# ESP32_can.net
KiCad netlist of a schematic drawn in EasyEDA Pro
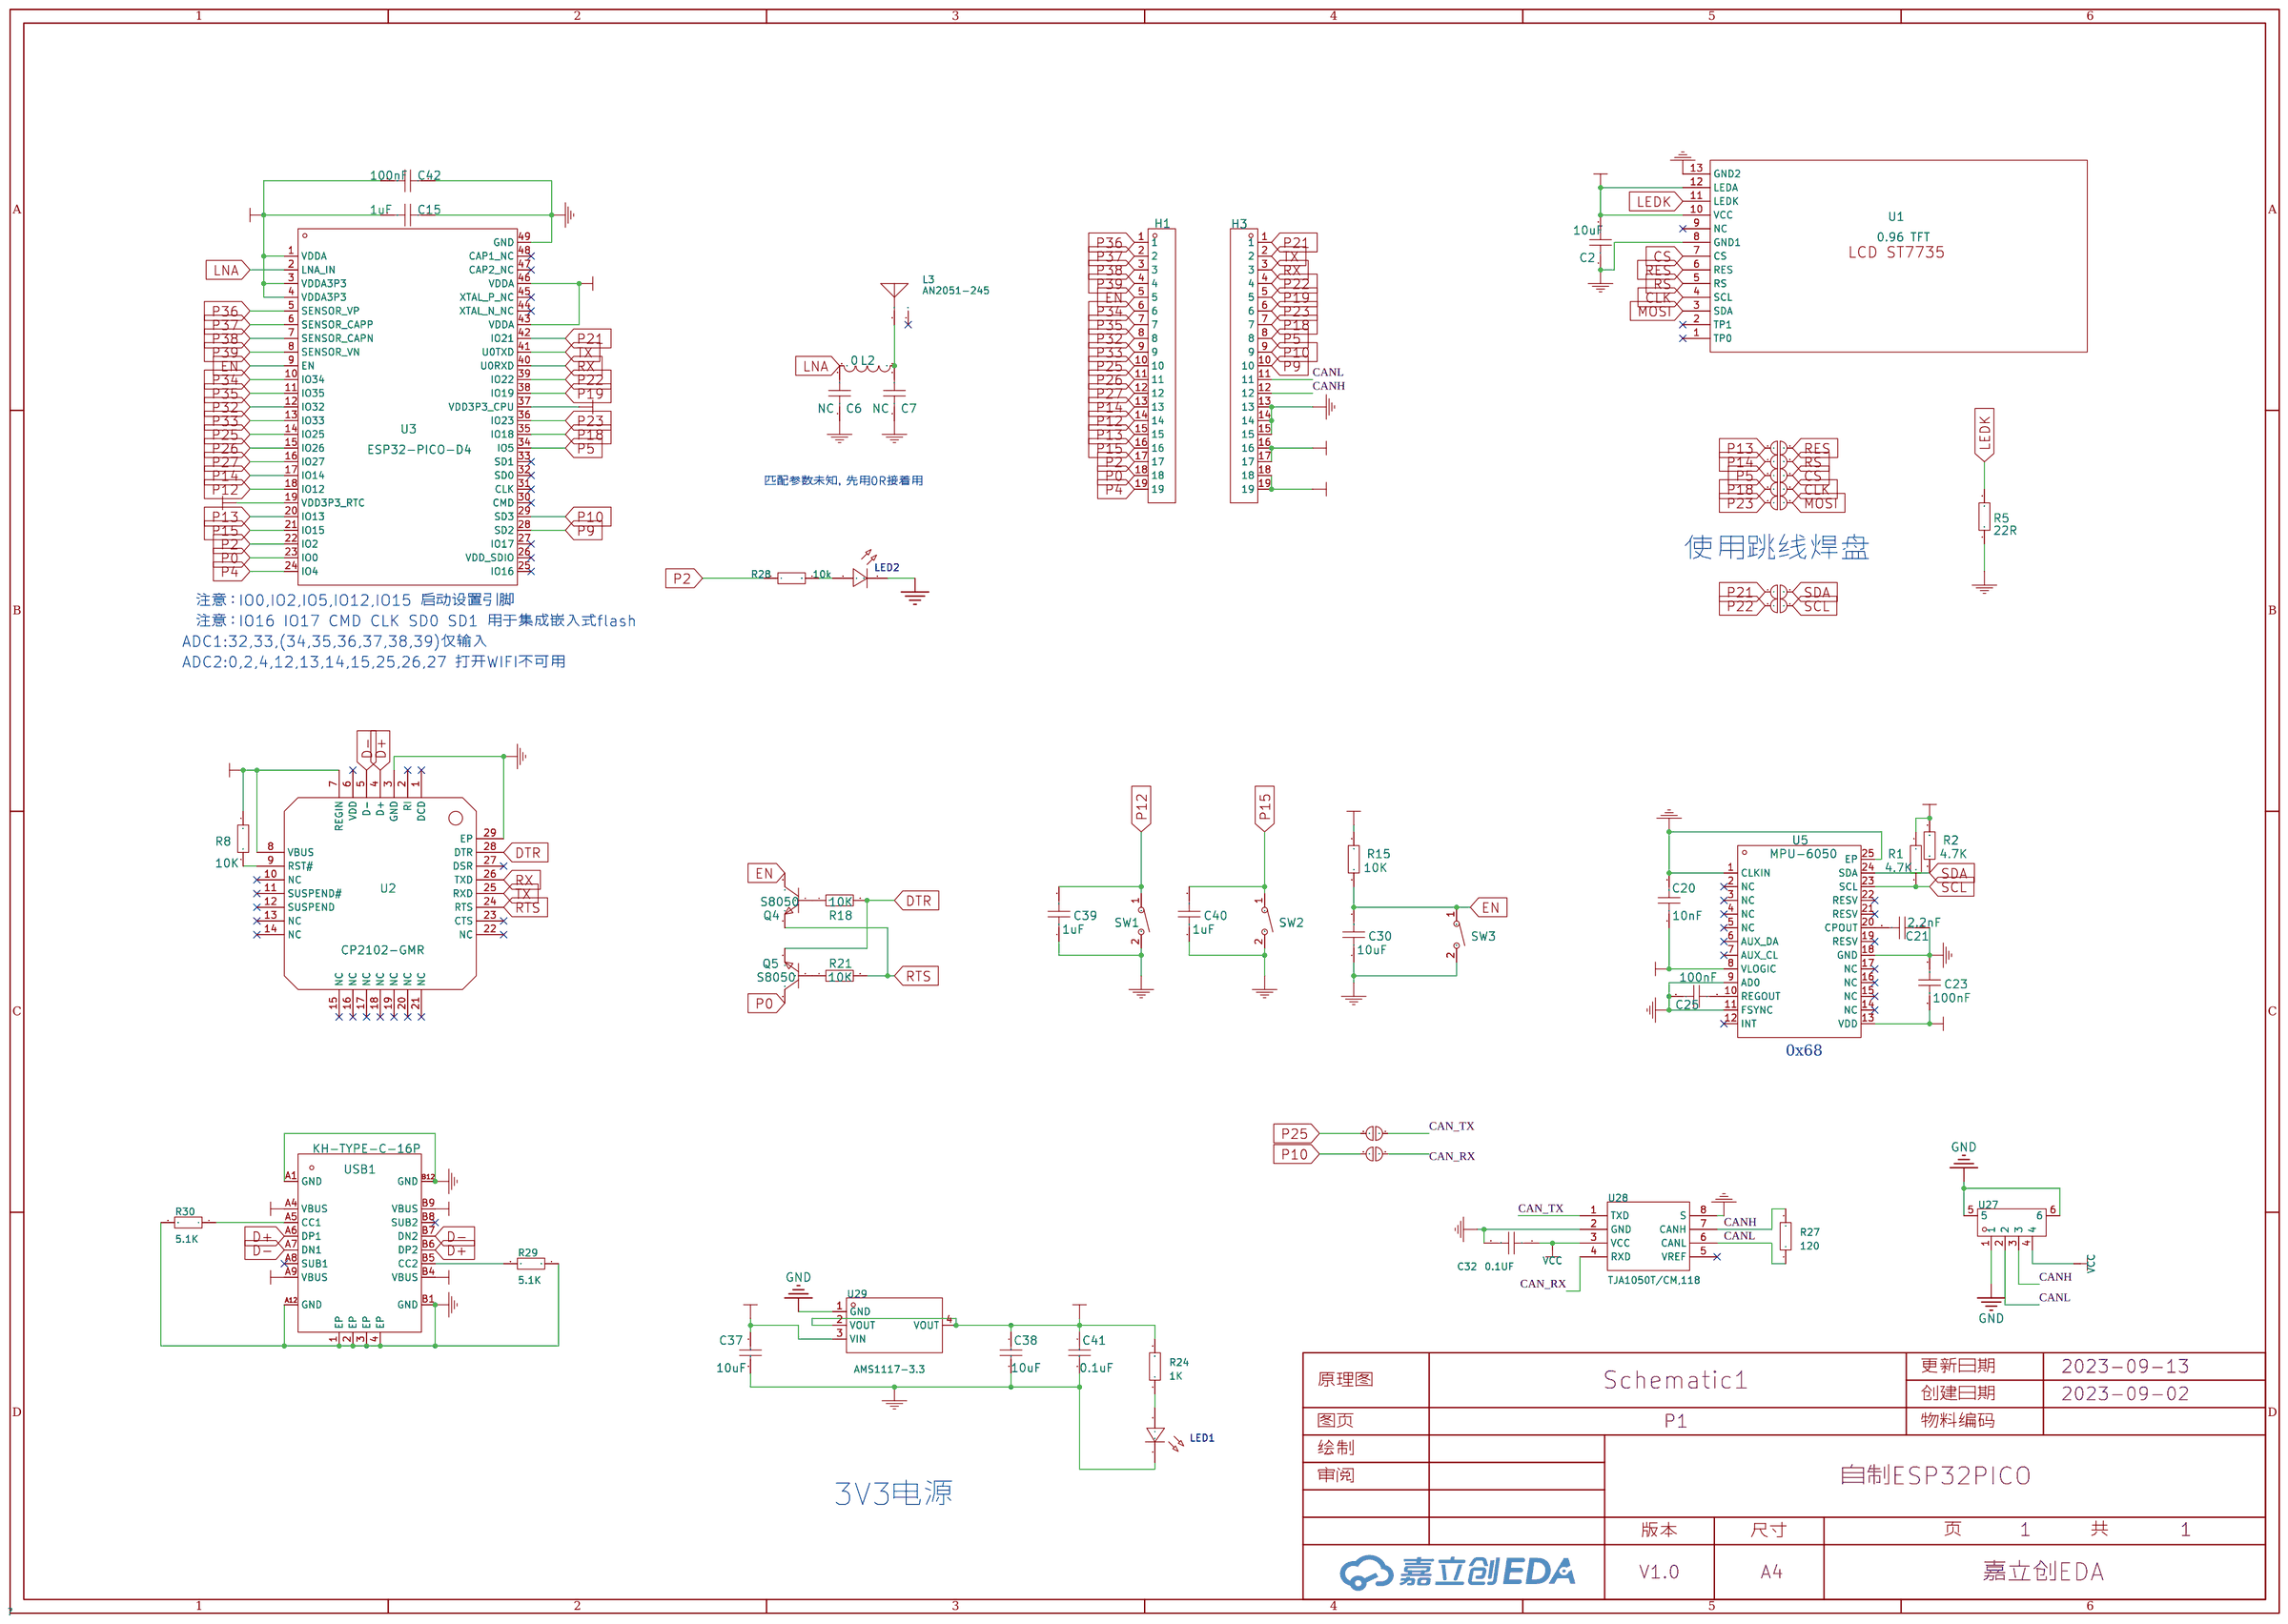
[diagram p0: schematic sheet]

(export (version "E")
  (design (tool "Eeschema 10.0.6"))
  (components
    (comp (ref "C2")
      (value "10uF")
      (footprint "easyedapro:C0603")
      (fields (field (name "Manufacturer Part") "CL10B104KC8NNNC") (field (name "Manufacturer") "SAMSUNG"))
      (libsource (lib "") (part "10uF_1"))
    )
    (comp (ref "C6")
      (value "NC")
      (footprint "easyedapro:C0402")
      (fields (field (name "Manufacturer Part") "GJM1555C1H1R2CB01D") (field (name "Manufacturer") "MuRata"))
      (libsource (lib "easyedapro") (part "NC"))
    )
    (comp (ref "C7")
      (value "NC")
      (footprint "easyedapro:C0402")
      (fields (field (name "Manufacturer Part") "GJM1555C1H1R2CB01D") (field (name "Manufacturer") "MuRata"))
      (libsource (lib "easyedapro") (part "NC"))
    )
    (comp (ref "C15")
      (value "1uF")
      (footprint "easyedapro:C0603")
      (fields (field (name "Manufacturer Part") "CL10B104KC8NNNC") (field (name "Manufacturer") "SAMSUNG"))
      (libsource (lib "easyedapro") (part "100nF"))
    )
    (comp (ref "C20")
      (value "10nF")
      (footprint "easyedapro:C0603")
      (fields (field (name "Manufacturer Part") "CL10B104KC8NNNC") (field (name "Manufacturer") "SAMSUNG"))
      (libsource (lib "easyedapro") (part "10nF"))
    )
    (comp (ref "C21")
      (value "2.2nF")
      (footprint "easyedapro:C0603")
      (fields (field (name "Manufacturer Part") "CL10B104KC8NNNC") (field (name "Manufacturer") "SAMSUNG"))
      (libsource (lib "easyedapro") (part "2.2nF"))
    )
    (comp (ref "C23")
      (value "100nF")
      (footprint "easyedapro:C0603")
      (fields (field (name "Manufacturer Part") "CL10B104KC8NNNC") (field (name "Manufacturer") "SAMSUNG"))
      (libsource (lib "easyedapro") (part "100nF"))
    )
    (comp (ref "C25")
      (value "100nF")
      (footprint "easyedapro:C0603")
      (fields (field (name "Manufacturer Part") "CL10B104KC8NNNC") (field (name "Manufacturer") "SAMSUNG"))
      (libsource (lib "easyedapro") (part "100nF"))
    )
    (comp (ref "C30")
      (value "10uF")
      (footprint "easyedapro:C0603")
      (fields (field (name "Manufacturer Part") "CL10B104KC8NNNC") (field (name "Manufacturer") "SAMSUNG"))
      (libsource (lib "easyedapro") (part "1uF"))
    )
    (comp (ref "C32")
      (value "0.1UF")
      (footprint "easyedapro:C0805")
      (libsource (lib "easyedapro") (part "CapAcitance"))
    )
    (comp (ref "C37")
      (value "10uF")
      (footprint "easyedapro:C0603")
      (fields (field (name "Manufacturer Part") "0603F105M160NT") (field (name "Manufacturer") "FH"))
      (libsource (lib "easyedapro") (part "10uF"))
    )
    (comp (ref "C38")
      (value "10uF")
      (footprint "easyedapro:C0603")
      (fields (field (name "Manufacturer Part") "0603F105M160NT") (field (name "Manufacturer") "FH"))
      (libsource (lib "easyedapro") (part "10uF"))
    )
    (comp (ref "C39")
      (value "1uF")
      (footprint "easyedapro:C0603")
      (fields (field (name "Manufacturer Part") "CL10B104KC8NNNC") (field (name "Manufacturer") "SAMSUNG"))
      (libsource (lib "easyedapro") (part "1uF"))
    )
    (comp (ref "C40")
      (value "1uF")
      (footprint "easyedapro:C0603")
      (fields (field (name "Manufacturer Part") "CL10B104KC8NNNC") (field (name "Manufacturer") "SAMSUNG"))
      (libsource (lib "easyedapro") (part "1uF"))
    )
    (comp (ref "C41")
      (value "0.1uF")
      (footprint "easyedapro:C0603")
      (fields (field (name "Manufacturer Part") "0603F105M160NT") (field (name "Manufacturer") "FH"))
      (libsource (lib "easyedapro") (part "10uF"))
    )
    (comp (ref "C42")
      (value "100nF")
      (footprint "easyedapro:C0603")
      (fields (field (name "Manufacturer Part") "CL10B104KC8NNNC") (field (name "Manufacturer") "SAMSUNG"))
      (libsource (lib "easyedapro") (part "100nF"))
    )
    (comp (ref "H1")
      (value "X6511WV-19H-C30D60")
      (footprint "easyedapro:HDR-TH_19P-P2.54-V-M")
      (fields (field (name "Manufacturer") "XKB Connectivity"))
      (libsource (lib "easyedapro") (part "X6511WV-19H-C30D60"))
    )
    (comp (ref "H3")
      (value "X6511WV-19H-C30D60")
      (footprint "easyedapro:HDR-TH_19P-P2.54-V-M")
      (fields (field (name "Manufacturer") "XKB Connectivity"))
      (libsource (lib "easyedapro") (part "X6511WV-19H-C30D60"))
    )
    (comp (ref "J2")
      (value "跳线焊盘")
      (footprint "easyedapro:0402L焊盘")
      (libsource (lib "easyedapro") (part "跳线焊盘"))
    )
    (comp (ref "J3")
      (value "跳线焊盘")
      (footprint "easyedapro:0402L焊盘")
      (libsource (lib "easyedapro") (part "跳线焊盘"))
    )
    (comp (ref "J4")
      (value "跳线焊盘")
      (footprint "easyedapro:0402L焊盘")
      (libsource (lib "easyedapro") (part "跳线焊盘"))
    )
    (comp (ref "J5")
      (value "跳线焊盘")
      (footprint "easyedapro:0402L焊盘")
      (libsource (lib "easyedapro") (part "跳线焊盘"))
    )
    (comp (ref "J6")
      (value "跳线焊盘")
      (footprint "easyedapro:0402L焊盘")
      (libsource (lib "easyedapro") (part "跳线焊盘"))
    )
    (comp (ref "J7")
      (value "跳线焊盘")
      (footprint "easyedapro:0402L焊盘")
      (libsource (lib "easyedapro") (part "跳线焊盘"))
    )
    (comp (ref "J8")
      (value "跳线焊盘")
      (footprint "easyedapro:0402L焊盘")
      (libsource (lib "easyedapro") (part "跳线焊盘"))
    )
    (comp (ref "J9")
      (value "跳线焊盘")
      (footprint "easyedapro:0402L焊盘")
      (libsource (lib "easyedapro") (part "跳线焊盘"))
    )
    (comp (ref "J10")
      (value "跳线焊盘")
      (footprint "easyedapro:0402L焊盘")
      (libsource (lib "easyedapro") (part "跳线焊盘"))
    )
    (comp (ref "L2")
      (value "0")
      (footprint "easyedapro:L0402")
      (fields (field (name "Manufacturer Part") "LQG15HS2N4S02D") (field (name "Manufacturer") "MuRata"))
      (libsource (lib "easyedapro") (part "0"))
    )
    (comp (ref "L3")
      (value "AN2051-245")
      (footprint "easyedapro:ANT2051")
      (description "小体积，高增益，WIFI，蓝牙，zigBee 2.4G天线")
      (fields (field (name "Manufacturer") "rainsun(霖昱微)"))
      (libsource (lib "easyedapro") (part "AN2051-245"))
    )
    (comp (ref "LED1")
      (value "~")
      (footprint "easyedapro:LED_0603")
      (libsource (lib "easyedapro") (part "LED_G"))
    )
    (comp (ref "LED2")
      (value "~")
      (footprint "easyedapro:LED_0603")
      (libsource (lib "easyedapro") (part "LED_G"))
    )
    (comp (ref "Q4")
      (value "S8050")
      (footprint "easyedapro:SOT-23-3_L2.9-W1.3-P1.90-LS2.4-BR")
      (fields (field (name "Manufacturer") "WPMtek(维攀微)"))
      (libsource (lib "") (part "S8050_1"))
    )
    (comp (ref "Q5")
      (value "S8050")
      (footprint "easyedapro:SOT-23-3_L2.9-W1.3-P1.90-LS2.4-BR")
      (fields (field (name "Manufacturer") "WPMtek(维攀微)"))
      (libsource (lib "easyedapro") (part "S8050"))
    )
    (comp (ref "R1")
      (value "4.7K")
      (footprint "easyedapro:R0603")
      (fields (field (name "Manufacturer Part") "RTT031002FTP") (field (name "Manufacturer") "RALEC"))
      (libsource (lib "easyedapro") (part "4.7K"))
    )
    (comp (ref "R2")
      (value "4.7K")
      (footprint "easyedapro:R0603")
      (fields (field (name "Manufacturer Part") "RTT031002FTP") (field (name "Manufacturer") "RALEC"))
      (libsource (lib "easyedapro") (part "4.7K"))
    )
    (comp (ref "R5")
      (value "22R")
      (footprint "easyedapro:R0603")
      (fields (field (name "Manufacturer Part") "0603WAJ0000T5E") (field (name "Manufacturer") "UniOhm"))
      (libsource (lib "easyedapro") (part "22R"))
    )
    (comp (ref "R8")
      (value "10K")
      (footprint "easyedapro:R0603")
      (fields (field (name "Manufacturer Part") "0603WAJ0000T5E") (field (name "Manufacturer") "UniOhm"))
      (libsource (lib "easyedapro") (part "10K"))
    )
    (comp (ref "R15")
      (value "10K")
      (footprint "easyedapro:R0603")
      (fields (field (name "Manufacturer Part") "RTT031002FTP") (field (name "Manufacturer") "RALEC"))
      (libsource (lib "easyedapro") (part "10K"))
    )
    (comp (ref "R18")
      (value "10K")
      (footprint "easyedapro:R0603")
      (fields (field (name "Manufacturer Part") "0603WAJ0000T5E") (field (name "Manufacturer") "UniOhm"))
      (libsource (lib "easyedapro") (part "10K"))
    )
    (comp (ref "R21")
      (value "10K")
      (footprint "easyedapro:R0603")
      (fields (field (name "Manufacturer Part") "0603WAJ0000T5E") (field (name "Manufacturer") "UniOhm"))
      (libsource (lib "easyedapro") (part "10K"))
    )
    (comp (ref "R24") (value "1K") (footprint "easyedapro:R0805") (libsource (lib "easyedapro") (part "电阻")))
    (comp (ref "R27") (value "120") (footprint "easyedapro:R0805") (libsource (lib "easyedapro") (part "电阻")))
    (comp (ref "R28") (value "10k") (footprint "easyedapro:R0805") (libsource (lib "easyedapro") (part "电阻")))
    (comp (ref "R29")
      (value "5.1K")
      (footprint "easyedapro:R0805")
      (libsource (lib "easyedapro") (part "电阻"))
    )
    (comp (ref "R30")
      (value "5.1K")
      (footprint "easyedapro:R0805")
      (libsource (lib "easyedapro") (part "电阻"))
    )
    (comp (ref "SW1")
      (value "TS342A2P-WZ")
      (footprint "easyedapro:SW-SMD_L4.0-W2.9-LS5.0")
      (fields (field (name "Manufacturer") "SHOU HAN"))
      (libsource (lib "easyedapro") (part "TS342A2P-WZ"))
    )
    (comp (ref "SW2")
      (value "TS342A2P-WZ")
      (footprint "easyedapro:SW-SMD_L4.0-W2.9-LS5.0")
      (fields (field (name "Manufacturer") "SHOU HAN"))
      (libsource (lib "easyedapro") (part "TS342A2P-WZ"))
    )
    (comp (ref "SW3")
      (value "TS342A2P-WZ")
      (footprint "easyedapro:SW-SMD_L4.0-W2.9-LS5.0")
      (fields (field (name "Manufacturer") "SHOU HAN"))
      (libsource (lib "easyedapro") (part "TS342A2P-WZ"))
    )
    (comp (ref "U1")
      (value "0.96 TFT")
      (footprint "easyedapro:0.96 LCD")
      (libsource (lib "easyedapro") (part "0.96 TFT"))
    )
    (comp (ref "U2")
      (value "CP2102-GMR")
      (footprint "easyedapro:QFN-28_L5.0-W5.0-P0.50-BL-EP")
      (fields (field (name "Manufacturer") "SILICON LABS"))
      (libsource (lib "easyedapro") (part "CP2102-GMR"))
    )
    (comp (ref "U3")
      (value "ESP32-PICO-D4")
      (footprint "easyedapro:QFN-48_L7.0-W7.0-P0.50-BL-EP5.1")
      (fields (field (name "Manufacturer") "Espressif Systems"))
      (libsource (lib "easyedapro") (part "ESP32-PICO-D4"))
    )
    (comp (ref "U5")
      (value "MPU-6050")
      (footprint "easyedapro:QFN-24_L4.0-W4.0-P0.50-BL-EP2.6")
      (fields (field (name "Manufacturer") "InvenSense"))
      (libsource (lib "easyedapro") (part "MPU-6050"))
    )
    (comp (ref "U27")
      (value "SH1.0-4P")
      (footprint "easyedapro:CONN-SMD_4P-P1.00_SH1.0-4P")
      (libsource (lib "easyedapro") (part "SH1.0-4P"))
    )
    (comp (ref "U28")
      (value "TJA1050T/CM,118")
      (footprint "easyedapro:SOIC-8_L5.0-W4.0-P1.27-LS6.0-BL")
      (description "类型:收发器;")
      (fields (field (name "Manufacturer") "NXP(恩智浦)"))
      (libsource (lib "easyedapro") (part "TJA1050T/CM,118"))
    )
    (comp (ref "U29")
      (value "AMS1117-3.3")
      (footprint "easyedapro:SOT-223-3_L6.5-W3.4-P2.30-LS7.0-BR")
      (description "输出类型:固定;输出极性:正;最大输入电压:-;输出电压:3.3V;输出电流:1A;电源纹波抑制比(PSRR):72dB@(120Hz);")
      (fields (field (name "Manufacturer") "AMS"))
      (libsource (lib "easyedapro") (part "AMS1117-3.3"))
    )
    (comp (ref "USB1")
      (value "KH-TYPE-C-16P")
      (footprint "easyedapro:USB-C-SMD_KH-TYPE-C-16P")
      (fields (field (name "Manufacturer") "Shenzhen Kinghelm Elec"))
      (libsource (lib "easyedapro") (part "KH-TYPE-C-16P"))
    )
  )
  (nets
    (net (code "1") (name "/CANH") (class "Default")
      (node (ref "H3") (pin "12") (pinfunction "12_12") (pintype "input"))
      (node (ref "R27") (pin "2") (pinfunction "2_2") (pintype "input"))
      (node (ref "U27") (pin "3") (pinfunction "3_3") (pintype "input"))
      (node (ref "U28") (pin "7") (pinfunction "CANH_7") (pintype "input"))
    )
    (net (code "2") (name "/CANL") (class "Default")
      (node (ref "H3") (pin "11") (pinfunction "11_11") (pintype "input"))
      (node (ref "R27") (pin "1") (pinfunction "1_1") (pintype "input"))
      (node (ref "U27") (pin "2") (pinfunction "2_2") (pintype "input"))
      (node (ref "U28") (pin "6") (pinfunction "CANL_6") (pintype "input"))
    )
    (net (code "3") (name "/CAN_RX") (class "Default")
      (node (ref "J10") (pin "2") (pinfunction "2_2") (pintype "input"))
      (node (ref "U28") (pin "4") (pinfunction "RXD_4") (pintype "input"))
    )
    (net (code "4") (name "/CAN_TX") (class "Default")
      (node (ref "J9") (pin "2") (pinfunction "2_2") (pintype "input"))
      (node (ref "U28") (pin "1") (pinfunction "TXD_1") (pintype "input"))
    )
    (net (code "5") (name "3V3") (class "Default")
      (node (ref "C15") (pin "2") (pinfunction "2_2") (pintype "input"))
      (node (ref "C2") (pin "2") (pinfunction "2_2") (pintype "input"))
      (node (ref "C20") (pin "1") (pinfunction "1_1") (pintype "input"))
      (node (ref "C23") (pin "1") (pinfunction "1_1") (pintype "input"))
      (node (ref "C38") (pin "1") (pinfunction "1_1") (pintype "input"))
      (node (ref "C41") (pin "1") (pinfunction "1_1") (pintype "input"))
      (node (ref "C42") (pin "2") (pinfunction "2_2") (pintype "input"))
      (node (ref "H3") (pin "16") (pinfunction "16_16") (pintype "input"))
      (node (ref "H3") (pin "17") (pinfunction "17_17") (pintype "input"))
      (node (ref "R1") (pin "1") (pinfunction "1_1") (pintype "input"))
      (node (ref "R15") (pin "1") (pinfunction "1_1") (pintype "input"))
      (node (ref "R2") (pin "1") (pinfunction "1_1") (pintype "input"))
      (node (ref "R24") (pin "2") (pinfunction "2_2") (pintype "input"))
      (node (ref "U1") (pin "10") (pinfunction "VCC_10") (pintype "input"))
      (node (ref "U1") (pin "12") (pinfunction "LEDA_12") (pintype "input"))
      (node (ref "U29") (pin "2") (pinfunction "VOUT_2") (pintype "input"))
      (node (ref "U29") (pin "4") (pinfunction "VOUT_4") (pintype "input"))
      (node (ref "U3") (pin "1") (pinfunction "VDDA_1") (pintype "input"))
      (node (ref "U3") (pin "19") (pinfunction "VDD3P3_RTC_19") (pintype "input"))
      (node (ref "U3") (pin "3") (pinfunction "VDDA3P3_3") (pintype "input"))
      (node (ref "U3") (pin "37") (pinfunction "VDD3P3_CPU_37") (pintype "input"))
      (node (ref "U3") (pin "4") (pinfunction "VDDA3P3_4") (pintype "input"))
      (node (ref "U3") (pin "43") (pinfunction "VDDA_43") (pintype "input"))
      (node (ref "U3") (pin "46") (pinfunction "VDDA_46") (pintype "input"))
      (node (ref "U5") (pin "13") (pinfunction "VDD_13") (pintype "input"))
      (node (ref "U5") (pin "8") (pinfunction "VLOGIC_8") (pintype "input"))
    )
    (net (code "6") (name "CLK") (class "Default")
      (node (ref "J5") (pin "2") (pinfunction "2_2") (pintype "input"))
      (node (ref "U1") (pin "4") (pinfunction "SCL_4") (pintype "input"))
    )
    (net (code "7") (name "CS") (class "Default")
      (node (ref "J2") (pin "2") (pinfunction "2_2") (pintype "input"))
      (node (ref "U1") (pin "7") (pinfunction "CS_7") (pintype "input"))
    )
    (net (code "8") (name "D+") (class "Default")
      (node (ref "U2") (pin "4") (pinfunction "D+_4") (pintype "input"))
      (node (ref "USB1") (pin "A6") (pinfunction "DP1_A6") (pintype "input"))
      (node (ref "USB1") (pin "B6") (pinfunction "DP2_B6") (pintype "input"))
    )
    (net (code "9") (name "D-") (class "Default")
      (node (ref "U2") (pin "5") (pinfunction "D-_5") (pintype "input"))
      (node (ref "USB1") (pin "A7") (pinfunction "DN1_A7") (pintype "input"))
      (node (ref "USB1") (pin "B7") (pinfunction "DN2_B7") (pintype "input"))
    )
    (net (code "10") (name "DTR") (class "Default")
      (node (ref "Q5") (pin "2") (pinfunction "E_2") (pintype "input"))
      (node (ref "R18") (pin "2") (pinfunction "2_2") (pintype "input"))
      (node (ref "U2") (pin "28") (pinfunction "DTR_28") (pintype "input"))
    )
    (net (code "11") (name "EN") (class "Default")
      (node (ref "C30") (pin "2") (pinfunction "2_2") (pintype "input"))
      (node (ref "H1") (pin "5") (pinfunction "5_5") (pintype "input"))
      (node (ref "Q4") (pin "3") (pinfunction "C_3") (pintype "input"))
      (node (ref "R15") (pin "2") (pinfunction "2_2") (pintype "input"))
      (node (ref "SW3") (pin "1") (pinfunction "1_1") (pintype "input"))
      (node (ref "U3") (pin "9") (pinfunction "EN_9") (pintype "input"))
    )
    (net (code "12") (name "GND") (class "Default")
      (node (ref "C15") (pin "1") (pinfunction "1_1") (pintype "input"))
      (node (ref "C2") (pin "1") (pinfunction "1_1") (pintype "input"))
      (node (ref "C20") (pin "2") (pinfunction "2_2") (pintype "input"))
      (node (ref "C21") (pin "1") (pinfunction "1_1") (pintype "input"))
      (node (ref "C23") (pin "2") (pinfunction "2_2") (pintype "input"))
      (node (ref "C25") (pin "2") (pinfunction "2_2") (pintype "input"))
      (node (ref "C30") (pin "1") (pinfunction "1_1") (pintype "input"))
      (node (ref "C32") (pin "2") (pinfunction "2_2") (pintype "input"))
      (node (ref "C37") (pin "2") (pinfunction "2_2") (pintype "input"))
      (node (ref "C38") (pin "2") (pinfunction "2_2") (pintype "input"))
      (node (ref "C39") (pin "1") (pinfunction "1_1") (pintype "input"))
      (node (ref "C40") (pin "1") (pinfunction "1_1") (pintype "input"))
      (node (ref "C41") (pin "2") (pinfunction "2_2") (pintype "input"))
      (node (ref "C42") (pin "1") (pinfunction "1_1") (pintype "input"))
      (node (ref "C6") (pin "1") (pinfunction "1_1") (pintype "input"))
      (node (ref "C7") (pin "1") (pinfunction "1_1") (pintype "input"))
      (node (ref "H3") (pin "13") (pinfunction "13_13") (pintype "input"))
      (node (ref "H3") (pin "14") (pinfunction "14_14") (pintype "input"))
      (node (ref "H3") (pin "15") (pinfunction "15_15") (pintype "input"))
      (node (ref "LED1") (pin "1") (pinfunction "C_1") (pintype "input"))
      (node (ref "LED2") (pin "1") (pinfunction "C_1") (pintype "input"))
      (node (ref "R29") (pin "1") (pinfunction "1_1") (pintype "input"))
      (node (ref "R30") (pin "2") (pinfunction "2_2") (pintype "input"))
      (node (ref "R5") (pin "1") (pinfunction "1_1") (pintype "input"))
      (node (ref "SW1") (pin "2") (pinfunction "2_2") (pintype "input"))
      (node (ref "SW2") (pin "2") (pinfunction "2_2") (pintype "input"))
      (node (ref "SW3") (pin "2") (pinfunction "2_2") (pintype "input"))
      (node (ref "U1") (pin "13") (pinfunction "GND2_13") (pintype "input"))
      (node (ref "U1") (pin "8") (pinfunction "GND1_8") (pintype "input"))
      (node (ref "U2") (pin "29") (pinfunction "EP_29") (pintype "input"))
      (node (ref "U2") (pin "3") (pinfunction "GND_3") (pintype "input"))
      (node (ref "U27") (pin "1") (pinfunction "1_1") (pintype "input"))
      (node (ref "U27") (pin "5") (pinfunction "5_5") (pintype "input"))
      (node (ref "U27") (pin "6") (pinfunction "6_6") (pintype "input"))
      (node (ref "U28") (pin "2") (pinfunction "GND_2") (pintype "input"))
      (node (ref "U28") (pin "8") (pinfunction "S_8") (pintype "input"))
      (node (ref "U29") (pin "1") (pinfunction "GND_1") (pintype "input"))
      (node (ref "U3") (pin "49") (pinfunction "GND_49") (pintype "input"))
      (node (ref "U5") (pin "1") (pinfunction "CLKIN_1") (pintype "input"))
      (node (ref "U5") (pin "11") (pinfunction "FSYNC_11") (pintype "input"))
      (node (ref "U5") (pin "18") (pinfunction "GND_18") (pintype "input"))
      (node (ref "U5") (pin "25") (pinfunction "EP_25") (pintype "input"))
      (node (ref "U5") (pin "9") (pinfunction "AD0_9") (pintype "input"))
      (node (ref "USB1") (pin "1") (pinfunction "EP_1") (pintype "input"))
      (node (ref "USB1") (pin "2") (pinfunction "EP_2") (pintype "input"))
      (node (ref "USB1") (pin "3") (pinfunction "EP_3") (pintype "input"))
      (node (ref "USB1") (pin "4") (pinfunction "EP_4") (pintype "input"))
      (node (ref "USB1") (pin "A1") (pinfunction "GND_A1") (pintype "input"))
      (node (ref "USB1") (pin "A12") (pinfunction "GND_A12") (pintype "input"))
      (node (ref "USB1") (pin "B1") (pinfunction "GND_B1") (pintype "input"))
      (node (ref "USB1") (pin "B12") (pinfunction "GND_B12") (pintype "input"))
    )
    (net (code "13") (name "LEDK") (class "Default")
      (node (ref "R5") (pin "2") (pinfunction "2_2") (pintype "input"))
      (node (ref "U1") (pin "11") (pinfunction "LEDK_11") (pintype "input"))
    )
    (net (code "14") (name "LNA") (class "Default")
      (node (ref "C6") (pin "2") (pinfunction "2_2") (pintype "input"))
      (node (ref "L2") (pin "2") (pinfunction "2_2") (pintype "input"))
      (node (ref "U3") (pin "2") (pinfunction "LNA_IN_2") (pintype "input"))
    )
    (net (code "15") (name "MOSI") (class "Default")
      (node (ref "J6") (pin "2") (pinfunction "2_2") (pintype "input"))
      (node (ref "U1") (pin "3") (pinfunction "SDA_3") (pintype "input"))
    )
    (net (code "16") (name "Net-(L3-ANT)") (class "Default")
      (node (ref "C7") (pin "2") (pinfunction "2_2") (pintype "input"))
      (node (ref "L2") (pin "1") (pinfunction "1_1") (pintype "input"))
      (node (ref "L3") (pin "1") (pinfunction "ANT_1") (pintype "input"))
    )
    (net (code "17") (name "Net-(LED1-A)") (class "Default")
      (node (ref "LED1") (pin "2") (pinfunction "A_2") (pintype "input"))
      (node (ref "R24") (pin "1") (pinfunction "1_1") (pintype "input"))
    )
    (net (code "18") (name "Net-(LED2-A)") (class "Default")
      (node (ref "LED2") (pin "2") (pinfunction "A_2") (pintype "input"))
      (node (ref "R28") (pin "2") (pinfunction "2_2") (pintype "input"))
    )
    (net (code "19") (name "Net-(Q4-B)") (class "Default")
      (node (ref "Q4") (pin "1") (pinfunction "B_1") (pintype "input"))
      (node (ref "R18") (pin "1") (pinfunction "1_1") (pintype "input"))
    )
    (net (code "20") (name "Net-(Q5-B)") (class "Default")
      (node (ref "Q5") (pin "1") (pinfunction "B_1") (pintype "input"))
      (node (ref "R21") (pin "1") (pinfunction "1_1") (pintype "input"))
    )
    (net (code "21") (name "Net-(U2-RST#)") (class "Default")
      (node (ref "R8") (pin "2") (pinfunction "2_2") (pintype "input"))
      (node (ref "U2") (pin "9") (pinfunction "RST#_9") (pintype "input"))
    )
    (net (code "22") (name "Net-(U5-CPOUT)") (class "Default")
      (node (ref "C21") (pin "2") (pinfunction "2_2") (pintype "input"))
      (node (ref "U5") (pin "20") (pinfunction "CPOUT_20") (pintype "input"))
    )
    (net (code "23") (name "Net-(U5-REGOUT)") (class "Default")
      (node (ref "C25") (pin "1") (pinfunction "1_1") (pintype "input"))
      (node (ref "U5") (pin "10") (pinfunction "REGOUT_10") (pintype "input"))
    )
    (net (code "24") (name "Net-(USB1-CC1)") (class "Default")
      (node (ref "R30") (pin "1") (pinfunction "1_1") (pintype "input"))
      (node (ref "USB1") (pin "A5") (pinfunction "CC1_A5") (pintype "input"))
    )
    (net (code "25") (name "Net-(USB1-CC2)") (class "Default")
      (node (ref "R29") (pin "2") (pinfunction "2_2") (pintype "input"))
      (node (ref "USB1") (pin "B5") (pinfunction "CC2_B5") (pintype "input"))
    )
    (net (code "26") (name "P0") (class "Default")
      (node (ref "H1") (pin "18") (pinfunction "18_18") (pintype "input"))
      (node (ref "Q5") (pin "3") (pinfunction "C_3") (pintype "input"))
      (node (ref "U3") (pin "23") (pinfunction "IO0_23") (pintype "input"))
    )
    (net (code "27") (name "P2") (class "Default")
      (node (ref "H1") (pin "17") (pinfunction "17_17") (pintype "input"))
      (node (ref "R28") (pin "1") (pinfunction "1_1") (pintype "input"))
      (node (ref "U3") (pin "22") (pinfunction "IO2_22") (pintype "input"))
    )
    (net (code "28") (name "P4") (class "Default")
      (node (ref "H1") (pin "19") (pinfunction "19_19") (pintype "input"))
      (node (ref "U3") (pin "24") (pinfunction "IO4_24") (pintype "input"))
    )
    (net (code "29") (name "P5") (class "Default")
      (node (ref "H3") (pin "8") (pinfunction "8_8") (pintype "input"))
      (node (ref "J2") (pin "1") (pinfunction "1_1") (pintype "input"))
      (node (ref "U3") (pin "34") (pinfunction "IO5_34") (pintype "input"))
    )
    (net (code "30") (name "P9") (class "Default")
      (node (ref "H3") (pin "10") (pinfunction "10_10") (pintype "input"))
      (node (ref "U3") (pin "28") (pinfunction "SD2_28") (pintype "input"))
    )
    (net (code "31") (name "P10") (class "Default")
      (node (ref "H3") (pin "9") (pinfunction "9_9") (pintype "input"))
      (node (ref "J10") (pin "1") (pinfunction "1_1") (pintype "input"))
      (node (ref "U3") (pin "29") (pinfunction "SD3_29") (pintype "input"))
    )
    (net (code "32") (name "P12") (class "Default")
      (node (ref "C39") (pin "2") (pinfunction "2_2") (pintype "input"))
      (node (ref "H1") (pin "14") (pinfunction "14_14") (pintype "input"))
      (node (ref "SW1") (pin "1") (pinfunction "1_1") (pintype "input"))
      (node (ref "U3") (pin "18") (pinfunction "IO12_18") (pintype "input"))
    )
    (net (code "33") (name "P13") (class "Default")
      (node (ref "H1") (pin "15") (pinfunction "15_15") (pintype "input"))
      (node (ref "J3") (pin "1") (pinfunction "1_1") (pintype "input"))
      (node (ref "U3") (pin "20") (pinfunction "IO13_20") (pintype "input"))
    )
    (net (code "34") (name "P14") (class "Default")
      (node (ref "H1") (pin "13") (pinfunction "13_13") (pintype "input"))
      (node (ref "J4") (pin "1") (pinfunction "1_1") (pintype "input"))
      (node (ref "U3") (pin "17") (pinfunction "IO14_17") (pintype "input"))
    )
    (net (code "35") (name "P15") (class "Default")
      (node (ref "C40") (pin "2") (pinfunction "2_2") (pintype "input"))
      (node (ref "H1") (pin "16") (pinfunction "16_16") (pintype "input"))
      (node (ref "SW2") (pin "1") (pinfunction "1_1") (pintype "input"))
      (node (ref "U3") (pin "21") (pinfunction "IO15_21") (pintype "input"))
    )
    (net (code "36") (name "P18") (class "Default")
      (node (ref "H3") (pin "7") (pinfunction "7_7") (pintype "input"))
      (node (ref "J5") (pin "1") (pinfunction "1_1") (pintype "input"))
      (node (ref "U3") (pin "35") (pinfunction "IO18_35") (pintype "input"))
    )
    (net (code "37") (name "P19") (class "Default")
      (node (ref "H3") (pin "5") (pinfunction "5_5") (pintype "input"))
      (node (ref "U3") (pin "38") (pinfunction "IO19_38") (pintype "input"))
    )
    (net (code "38") (name "P21") (class "Default")
      (node (ref "H3") (pin "1") (pinfunction "1_1") (pintype "input"))
      (node (ref "J8") (pin "1") (pinfunction "1_1") (pintype "input"))
      (node (ref "U3") (pin "42") (pinfunction "IO21_42") (pintype "input"))
    )
    (net (code "39") (name "P22") (class "Default")
      (node (ref "H3") (pin "4") (pinfunction "4_4") (pintype "input"))
      (node (ref "J7") (pin "1") (pinfunction "1_1") (pintype "input"))
      (node (ref "U3") (pin "39") (pinfunction "IO22_39") (pintype "input"))
    )
    (net (code "40") (name "P23") (class "Default")
      (node (ref "H3") (pin "6") (pinfunction "6_6") (pintype "input"))
      (node (ref "J6") (pin "1") (pinfunction "1_1") (pintype "input"))
      (node (ref "U3") (pin "36") (pinfunction "IO23_36") (pintype "input"))
    )
    (net (code "41") (name "P25") (class "Default")
      (node (ref "H1") (pin "10") (pinfunction "10_10") (pintype "input"))
      (node (ref "J9") (pin "1") (pinfunction "1_1") (pintype "input"))
      (node (ref "U3") (pin "14") (pinfunction "IO25_14") (pintype "input"))
    )
    (net (code "42") (name "P26") (class "Default")
      (node (ref "H1") (pin "11") (pinfunction "11_11") (pintype "input"))
      (node (ref "U3") (pin "15") (pinfunction "IO26_15") (pintype "input"))
    )
    (net (code "43") (name "P27") (class "Default")
      (node (ref "H1") (pin "12") (pinfunction "12_12") (pintype "input"))
      (node (ref "U3") (pin "16") (pinfunction "IO27_16") (pintype "input"))
    )
    (net (code "44") (name "P32") (class "Default")
      (node (ref "H1") (pin "8") (pinfunction "8_8") (pintype "input"))
      (node (ref "U3") (pin "12") (pinfunction "IO32_12") (pintype "input"))
    )
    (net (code "45") (name "P33") (class "Default")
      (node (ref "H1") (pin "9") (pinfunction "9_9") (pintype "input"))
      (node (ref "U3") (pin "13") (pinfunction "IO33_13") (pintype "input"))
    )
    (net (code "46") (name "P34") (class "Default")
      (node (ref "H1") (pin "6") (pinfunction "6_6") (pintype "input"))
      (node (ref "U3") (pin "10") (pinfunction "IO34_10") (pintype "input"))
    )
    (net (code "47") (name "P35") (class "Default")
      (node (ref "H1") (pin "7") (pinfunction "7_7") (pintype "input"))
      (node (ref "U3") (pin "11") (pinfunction "IO35_11") (pintype "input"))
    )
    (net (code "48") (name "P36") (class "Default")
      (node (ref "H1") (pin "1") (pinfunction "1_1") (pintype "input"))
      (node (ref "U3") (pin "5") (pinfunction "SENSOR_VP_5") (pintype "input"))
    )
    (net (code "49") (name "P37") (class "Default")
      (node (ref "H1") (pin "2") (pinfunction "2_2") (pintype "input"))
      (node (ref "U3") (pin "6") (pinfunction "SENSOR_CAPP_6") (pintype "input"))
    )
    (net (code "50") (name "P38") (class "Default")
      (node (ref "H1") (pin "3") (pinfunction "3_3") (pintype "input"))
      (node (ref "U3") (pin "7") (pinfunction "SENSOR_CAPN_7") (pintype "input"))
    )
    (net (code "51") (name "P39") (class "Default")
      (node (ref "H1") (pin "4") (pinfunction "4_4") (pintype "input"))
      (node (ref "U3") (pin "8") (pinfunction "SENSOR_VN_8") (pintype "input"))
    )
    (net (code "52") (name "RES") (class "Default")
      (node (ref "J3") (pin "2") (pinfunction "2_2") (pintype "input"))
      (node (ref "U1") (pin "6") (pinfunction "RES_6") (pintype "input"))
    )
    (net (code "53") (name "RS") (class "Default")
      (node (ref "J4") (pin "2") (pinfunction "2_2") (pintype "input"))
      (node (ref "U1") (pin "5") (pinfunction "RS_5") (pintype "input"))
    )
    (net (code "54") (name "RTS") (class "Default")
      (node (ref "Q4") (pin "2") (pinfunction "E_2") (pintype "input"))
      (node (ref "R21") (pin "2") (pinfunction "2_2") (pintype "input"))
      (node (ref "U2") (pin "24") (pinfunction "RTS_24") (pintype "input"))
    )
    (net (code "55") (name "RX") (class "Default")
      (node (ref "H3") (pin "3") (pinfunction "3_3") (pintype "input"))
      (node (ref "U2") (pin "26") (pinfunction "TXD_26") (pintype "input"))
      (node (ref "U3") (pin "40") (pinfunction "U0RXD_40") (pintype "input"))
    )
    (net (code "56") (name "SCL") (class "Default")
      (node (ref "J7") (pin "2") (pinfunction "2_2") (pintype "input"))
      (node (ref "R1") (pin "2") (pinfunction "2_2") (pintype "input"))
      (node (ref "U5") (pin "23") (pinfunction "SCL_23") (pintype "input"))
    )
    (net (code "57") (name "SDA") (class "Default")
      (node (ref "J8") (pin "2") (pinfunction "2_2") (pintype "input"))
      (node (ref "R2") (pin "2") (pinfunction "2_2") (pintype "input"))
      (node (ref "U5") (pin "24") (pinfunction "SDA_24") (pintype "input"))
    )
    (net (code "58") (name "TX") (class "Default")
      (node (ref "H3") (pin "2") (pinfunction "2_2") (pintype "input"))
      (node (ref "U2") (pin "25") (pinfunction "RXD_25") (pintype "input"))
      (node (ref "U3") (pin "41") (pinfunction "U0TXD_41") (pintype "input"))
    )
    (net (code "59") (name "VCC") (class "Default")
      (node (ref "C32") (pin "1") (pinfunction "1_1") (pintype "input"))
      (node (ref "C37") (pin "1") (pinfunction "1_1") (pintype "input"))
      (node (ref "H3") (pin "18") (pinfunction "18_18") (pintype "input"))
      (node (ref "H3") (pin "19") (pinfunction "19_19") (pintype "input"))
      (node (ref "R8") (pin "1") (pinfunction "1_1") (pintype "input"))
      (node (ref "U2") (pin "7") (pinfunction "REGIN_7") (pintype "input"))
      (node (ref "U2") (pin "8") (pinfunction "VBUS_8") (pintype "input"))
      (node (ref "U27") (pin "4") (pinfunction "4_4") (pintype "input"))
      (node (ref "U28") (pin "3") (pinfunction "VCC_3") (pintype "input"))
      (node (ref "U29") (pin "3") (pinfunction "VIN_3") (pintype "input"))
      (node (ref "USB1") (pin "A4") (pinfunction "VBUS_A4") (pintype "input"))
      (node (ref "USB1") (pin "A9") (pinfunction "VBUS_A9") (pintype "input"))
      (node (ref "USB1") (pin "B4") (pinfunction "VBUS_B4") (pintype "input"))
      (node (ref "USB1") (pin "B9") (pinfunction "VBUS_B9") (pintype "input"))
    )
    (net (code "60") (name "unconnected-(L3-Pad2)") (class "Default")
      (node (ref "L3") (pin "2") (pinfunction "2_2") (pintype "input+no_connect"))
    )
    (net (code "61") (name "unconnected-(U1-NC-Pad9)") (class "Default")
      (node (ref "U1") (pin "9") (pinfunction "NC_9") (pintype "input+no_connect"))
    )
    (net (code "62") (name "unconnected-(U1-TP0-Pad1)") (class "Default")
      (node (ref "U1") (pin "1") (pinfunction "TP0_1") (pintype "input+no_connect"))
    )
    (net (code "63") (name "unconnected-(U1-TP1-Pad2)") (class "Default")
      (node (ref "U1") (pin "2") (pinfunction "TP1_2") (pintype "input+no_connect"))
    )
    (net (code "64") (name "unconnected-(U2-CTS-Pad23)") (class "Default")
      (node (ref "U2") (pin "23") (pinfunction "CTS_23") (pintype "input+no_connect"))
    )
    (net (code "65") (name "unconnected-(U2-DCD-Pad1)") (class "Default")
      (node (ref "U2") (pin "1") (pinfunction "DCD_1") (pintype "input+no_connect"))
    )
    (net (code "66") (name "unconnected-(U2-DSR-Pad27)") (class "Default")
      (node (ref "U2") (pin "27") (pinfunction "DSR_27") (pintype "input+no_connect"))
    )
    (net (code "67") (name "unconnected-(U2-NC-Pad10)") (class "Default")
      (node (ref "U2") (pin "10") (pinfunction "NC_10") (pintype "input+no_connect"))
    )
    (net (code "68") (name "unconnected-(U2-NC-Pad13)") (class "Default")
      (node (ref "U2") (pin "13") (pinfunction "NC_13") (pintype "input+no_connect"))
    )
    (net (code "69") (name "unconnected-(U2-NC-Pad14)") (class "Default")
      (node (ref "U2") (pin "14") (pinfunction "NC_14") (pintype "input+no_connect"))
    )
    (net (code "70") (name "unconnected-(U2-NC-Pad15)") (class "Default")
      (node (ref "U2") (pin "15") (pinfunction "NC_15") (pintype "input+no_connect"))
    )
    (net (code "71") (name "unconnected-(U2-NC-Pad16)") (class "Default")
      (node (ref "U2") (pin "16") (pinfunction "NC_16") (pintype "input+no_connect"))
    )
    (net (code "72") (name "unconnected-(U2-NC-Pad17)") (class "Default")
      (node (ref "U2") (pin "17") (pinfunction "NC_17") (pintype "input+no_connect"))
    )
    (net (code "73") (name "unconnected-(U2-NC-Pad18)") (class "Default")
      (node (ref "U2") (pin "18") (pinfunction "NC_18") (pintype "input+no_connect"))
    )
    (net (code "74") (name "unconnected-(U2-NC-Pad19)") (class "Default")
      (node (ref "U2") (pin "19") (pinfunction "NC_19") (pintype "input+no_connect"))
    )
    (net (code "75") (name "unconnected-(U2-NC-Pad20)") (class "Default")
      (node (ref "U2") (pin "20") (pinfunction "NC_20") (pintype "input+no_connect"))
    )
    (net (code "76") (name "unconnected-(U2-NC-Pad21)") (class "Default")
      (node (ref "U2") (pin "21") (pinfunction "NC_21") (pintype "input+no_connect"))
    )
    (net (code "77") (name "unconnected-(U2-NC-Pad22)") (class "Default")
      (node (ref "U2") (pin "22") (pinfunction "NC_22") (pintype "input+no_connect"))
    )
    (net (code "78") (name "unconnected-(U2-RI-Pad2)") (class "Default")
      (node (ref "U2") (pin "2") (pinfunction "RI_2") (pintype "input+no_connect"))
    )
    (net (code "79") (name "unconnected-(U2-SUSPEND#-Pad11)") (class "Default")
      (node (ref "U2") (pin "11") (pinfunction "SUSPEND#_11") (pintype "input+no_connect"))
    )
    (net (code "80") (name "unconnected-(U2-SUSPEND-Pad12)") (class "Default")
      (node (ref "U2") (pin "12") (pinfunction "SUSPEND_12") (pintype "input+no_connect"))
    )
    (net (code "81") (name "unconnected-(U2-VDD-Pad6)") (class "Default")
      (node (ref "U2") (pin "6") (pinfunction "VDD_6") (pintype "input+no_connect"))
    )
    (net (code "82") (name "unconnected-(U3-CAP1_NC-Pad48)") (class "Default")
      (node (ref "U3") (pin "48") (pinfunction "CAP1_NC_48") (pintype "input+no_connect"))
    )
    (net (code "83") (name "unconnected-(U3-CAP2_NC-Pad47)") (class "Default")
      (node (ref "U3") (pin "47") (pinfunction "CAP2_NC_47") (pintype "input+no_connect"))
    )
    (net (code "84") (name "unconnected-(U3-CLK-Pad31)") (class "Default")
      (node (ref "U3") (pin "31") (pinfunction "CLK_31") (pintype "input+no_connect"))
    )
    (net (code "85") (name "unconnected-(U3-CMD-Pad30)") (class "Default")
      (node (ref "U3") (pin "30") (pinfunction "CMD_30") (pintype "input+no_connect"))
    )
    (net (code "86") (name "unconnected-(U3-IO16-Pad25)") (class "Default")
      (node (ref "U3") (pin "25") (pinfunction "IO16_25") (pintype "input+no_connect"))
    )
    (net (code "87") (name "unconnected-(U3-IO17-Pad27)") (class "Default")
      (node (ref "U3") (pin "27") (pinfunction "IO17_27") (pintype "input+no_connect"))
    )
    (net (code "88") (name "unconnected-(U3-SD0-Pad32)") (class "Default")
      (node (ref "U3") (pin "32") (pinfunction "SD0_32") (pintype "input+no_connect"))
    )
    (net (code "89") (name "unconnected-(U3-SD1-Pad33)") (class "Default")
      (node (ref "U3") (pin "33") (pinfunction "SD1_33") (pintype "input+no_connect"))
    )
    (net (code "90") (name "unconnected-(U3-VDD_SDIO-Pad26)") (class "Default")
      (node (ref "U3") (pin "26") (pinfunction "VDD_SDIO_26") (pintype "input+no_connect"))
    )
    (net (code "91") (name "unconnected-(U3-XTAL_N_NC-Pad44)") (class "Default")
      (node (ref "U3") (pin "44") (pinfunction "XTAL_N_NC_44") (pintype "input+no_connect"))
    )
    (net (code "92") (name "unconnected-(U3-XTAL_P_NC-Pad45)") (class "Default")
      (node (ref "U3") (pin "45") (pinfunction "XTAL_P_NC_45") (pintype "input+no_connect"))
    )
    (net (code "93") (name "unconnected-(U5-AUX_CL-Pad7)") (class "Default")
      (node (ref "U5") (pin "7") (pinfunction "AUX_CL_7") (pintype "input+no_connect"))
    )
    (net (code "94") (name "unconnected-(U5-AUX_DA-Pad6)") (class "Default")
      (node (ref "U5") (pin "6") (pinfunction "AUX_DA_6") (pintype "input+no_connect"))
    )
    (net (code "95") (name "unconnected-(U5-INT-Pad12)") (class "Default")
      (node (ref "U5") (pin "12") (pinfunction "INT_12") (pintype "input+no_connect"))
    )
    (net (code "96") (name "unconnected-(U5-NC-Pad2)") (class "Default")
      (node (ref "U5") (pin "2") (pinfunction "NC_2") (pintype "input+no_connect"))
    )
    (net (code "97") (name "unconnected-(U5-NC-Pad3)") (class "Default")
      (node (ref "U5") (pin "3") (pinfunction "NC_3") (pintype "input+no_connect"))
    )
    (net (code "98") (name "unconnected-(U5-NC-Pad4)") (class "Default")
      (node (ref "U5") (pin "4") (pinfunction "NC_4") (pintype "input+no_connect"))
    )
    (net (code "99") (name "unconnected-(U5-NC-Pad5)") (class "Default")
      (node (ref "U5") (pin "5") (pinfunction "NC_5") (pintype "input+no_connect"))
    )
    (net (code "100") (name "unconnected-(U5-NC-Pad14)") (class "Default")
      (node (ref "U5") (pin "14") (pinfunction "NC_14") (pintype "input+no_connect"))
    )
    (net (code "101") (name "unconnected-(U5-NC-Pad15)") (class "Default")
      (node (ref "U5") (pin "15") (pinfunction "NC_15") (pintype "input+no_connect"))
    )
    (net (code "102") (name "unconnected-(U5-NC-Pad16)") (class "Default")
      (node (ref "U5") (pin "16") (pinfunction "NC_16") (pintype "input+no_connect"))
    )
    (net (code "103") (name "unconnected-(U5-NC-Pad17)") (class "Default")
      (node (ref "U5") (pin "17") (pinfunction "NC_17") (pintype "input+no_connect"))
    )
    (net (code "104") (name "unconnected-(U5-RESV-Pad19)") (class "Default")
      (node (ref "U5") (pin "19") (pinfunction "RESV_19") (pintype "input+no_connect"))
    )
    (net (code "105") (name "unconnected-(U5-RESV-Pad21)") (class "Default")
      (node (ref "U5") (pin "21") (pinfunction "RESV_21") (pintype "input+no_connect"))
    )
    (net (code "106") (name "unconnected-(U5-RESV-Pad22)") (class "Default")
      (node (ref "U5") (pin "22") (pinfunction "RESV_22") (pintype "input+no_connect"))
    )
    (net (code "107") (name "unconnected-(U28-VREF-Pad5)") (class "Default")
      (node (ref "U28") (pin "5") (pinfunction "VREF_5") (pintype "input+no_connect"))
    )
    (net (code "108") (name "unconnected-(USB1-SUB1-PadA8)") (class "Default")
      (node (ref "USB1") (pin "A8") (pinfunction "SUB1_A8") (pintype "input+no_connect"))
    )
    (net (code "109") (name "unconnected-(USB1-SUB2-PadB8)") (class "Default")
      (node (ref "USB1") (pin "B8") (pinfunction "SUB2_B8") (pintype "input+no_connect"))
    )
  )
)
